# TPS61230_v1_1.net
KiCad netlist of a schematic drawn in EAGLE
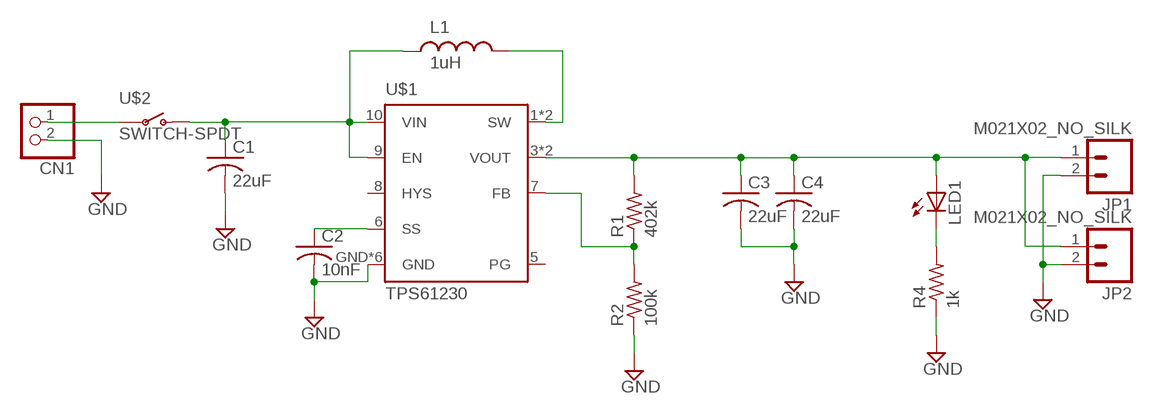
[diagram p0: schematic, sheet 1]

(export (version "E")
  (design (tool "Eeschema 10.0.6"))
  (components
    (comp (ref "C1")
      (value "22uF")
      (footprint "eagle-import:C0603K")
      (libsource (lib "eagle-import") (part "C-USC0603K"))
    )
    (comp (ref "C2")
      (value "10nF")
      (footprint "eagle-import:C0603K")
      (libsource (lib "eagle-import") (part "C-USC0603K"))
    )
    (comp (ref "C3")
      (value "22uF")
      (footprint "eagle-import:C0603K")
      (libsource (lib "eagle-import") (part "C-USC0603K"))
    )
    (comp (ref "C4")
      (value "22uF")
      (footprint "eagle-import:C0603K")
      (libsource (lib "eagle-import") (part "C-USC0603K"))
    )
    (comp (ref "CN1")
      (value "JST_2PIN-SMT-RA")
      (footprint "eagle-import:JST-PH-2-SMT-RA")
      (libsource (lib "eagle-import") (part "JST_2PIN-SMT-RA"))
    )
    (comp (ref "JP1")
      (value "M021X02_NO_SILK")
      (footprint "eagle-import:1X02_NO_SILK")
      (libsource (lib "eagle-import") (part "M021X02_NO_SILK"))
    )
    (comp (ref "JP2")
      (value "M021X02_NO_SILK")
      (footprint "eagle-import:1X02_NO_SILK")
      (libsource (lib "eagle-import") (part "M021X02_NO_SILK"))
    )
    (comp (ref "L1")
      (value "1uH")
      (footprint "eagle-import:XFL4020")
      (libsource (lib "eagle-import") (part "XFL4020"))
    )
    (comp (ref "LED1")
      (value "LEDCHIPLED_0603")
      (footprint "eagle-import:CHIPLED_0603")
      (libsource (lib "eagle-import") (part "LEDCHIPLED_0603"))
    )
    (comp (ref "R1")
      (value "402k")
      (footprint "eagle-import:R0603")
      (libsource (lib "eagle-import") (part "R-US_R0603"))
    )
    (comp (ref "R2")
      (value "100k")
      (footprint "eagle-import:R0603")
      (libsource (lib "eagle-import") (part "R-US_R0603"))
    )
    (comp (ref "R4")
      (value "1k")
      (footprint "eagle-import:R0603")
      (libsource (lib "eagle-import") (part "R-US_R0603"))
    )
    (comp (ref "U$1")
      (value "TPS61230")
      (footprint "eagle-import:DRC-S-PVSON-N11")
      (libsource (lib "eagle-import") (part "TPS61230"))
    )
    (comp (ref "U$2")
      (value "SWITCH-SPDT")
      (footprint "eagle-import:JS102011")
      (libsource (lib "eagle-import") (part "SWITCH-SPDT"))
    )
  )
  (nets
    (net (code "1") (name "/PG") (class "Default")
      (node (ref "U$1") (pin "5") (pinfunction "PG_5") (pintype "power_in"))
    )
    (net (code "2") (name "GND") (class "Default")
      (node (ref "C1") (pin "2") (pinfunction "2_2") (pintype "passive"))
      (node (ref "C2") (pin "2") (pinfunction "2_2") (pintype "passive"))
      (node (ref "C3") (pin "2") (pinfunction "2_2") (pintype "passive"))
      (node (ref "C4") (pin "2") (pinfunction "2_2") (pintype "passive"))
      (node (ref "CN1") (pin "2") (pinfunction "1_2") (pintype "passive"))
      (node (ref "JP1") (pin "2") (pinfunction "2_2") (pintype "passive"))
      (node (ref "JP2") (pin "2") (pinfunction "2_2") (pintype "passive"))
      (node (ref "R2") (pin "1") (pinfunction "1_1") (pintype "passive"))
      (node (ref "R4") (pin "1") (pinfunction "1_1") (pintype "passive"))
      (node (ref "U$1") (pin "GND") (pinfunction "GND_GND") (pintype "power_in"))
      (node (ref "U$1") (pin "GND@1") (pinfunction "GND_GND@1") (pintype "power_in"))
      (node (ref "U$1") (pin "GND@2") (pinfunction "GND_GND@2") (pintype "power_in"))
      (node (ref "U$1") (pin "GND@3") (pinfunction "GND_GND@3") (pintype "power_in"))
      (node (ref "U$1") (pin "GND@4") (pinfunction "GND_GND@4") (pintype "power_in"))
      (node (ref "U$1") (pin "GND@5") (pinfunction "GND_GND@5") (pintype "power_in"))
    )
    (net (code "3") (name "Net-(C3-Pad1)") (class "Default")
      (node (ref "C3") (pin "1") (pinfunction "1_1") (pintype "passive"))
      (node (ref "C4") (pin "1") (pinfunction "1_1") (pintype "passive"))
      (node (ref "JP1") (pin "1") (pinfunction "1_1") (pintype "passive"))
      (node (ref "JP2") (pin "1") (pinfunction "1_1") (pintype "passive"))
      (node (ref "LED1") (pin "A") (pinfunction "A_A") (pintype "passive"))
      (node (ref "R1") (pin "2") (pinfunction "2_2") (pintype "passive"))
      (node (ref "U$1") (pin "3") (pinfunction "VOUT_3") (pintype "passive"))
      (node (ref "U$1") (pin "4") (pinfunction "VOUT_4") (pintype "passive"))
    )
    (net (code "4") (name "Net-(CN1-2)") (class "Default")
      (node (ref "CN1") (pin "1") (pinfunction "2_1") (pintype "passive"))
      (node (ref "U$2") (pin "P$3") (pinfunction "P_P$3") (pintype "passive"))
    )
    (net (code "5") (name "Net-(L1-1)") (class "Default")
      (node (ref "C1") (pin "1") (pinfunction "1_1") (pintype "passive"))
      (node (ref "L1") (pin "P$1") (pinfunction "1_P$1") (pintype "passive"))
      (node (ref "U$1") (pin "10") (pinfunction "VIN_10") (pintype "input"))
      (node (ref "U$1") (pin "9") (pinfunction "EN_9") (pintype "input"))
      (node (ref "U$2") (pin "P$2") (pinfunction "O_P$2") (pintype "passive"))
    )
    (net (code "6") (name "Net-(L1-2)") (class "Default")
      (node (ref "L1") (pin "P$2") (pinfunction "2_P$2") (pintype "passive"))
      (node (ref "U$1") (pin "1") (pinfunction "SW_1") (pintype "input"))
      (node (ref "U$1") (pin "2") (pinfunction "SW_2") (pintype "input"))
    )
    (net (code "7") (name "Net-(LED1-PadC)") (class "Default")
      (node (ref "LED1") (pin "C") (pinfunction "C_C") (pintype "passive"))
      (node (ref "R4") (pin "2") (pinfunction "2_2") (pintype "passive"))
    )
    (net (code "8") (name "Net-(U$1-FB)") (class "Default")
      (node (ref "R1") (pin "1") (pinfunction "1_1") (pintype "passive"))
      (node (ref "R2") (pin "2") (pinfunction "2_2") (pintype "passive"))
      (node (ref "U$1") (pin "7") (pinfunction "FB_7") (pintype "input"))
    )
    (net (code "9") (name "Net-(U$1-SS)") (class "Default")
      (node (ref "C2") (pin "1") (pinfunction "1_1") (pintype "passive"))
      (node (ref "U$1") (pin "6") (pinfunction "SS_6") (pintype "input"))
    )
    (net (code "10") (name "unconnected-(U$1-HYS-Pad8)") (class "Default")
      (node (ref "U$1") (pin "8") (pinfunction "HYS_8") (pintype "input"))
    )
  )
)
